# BBB_Learning_Board_0B.net
KiCad netlist of a schematic drawn in EAGLE
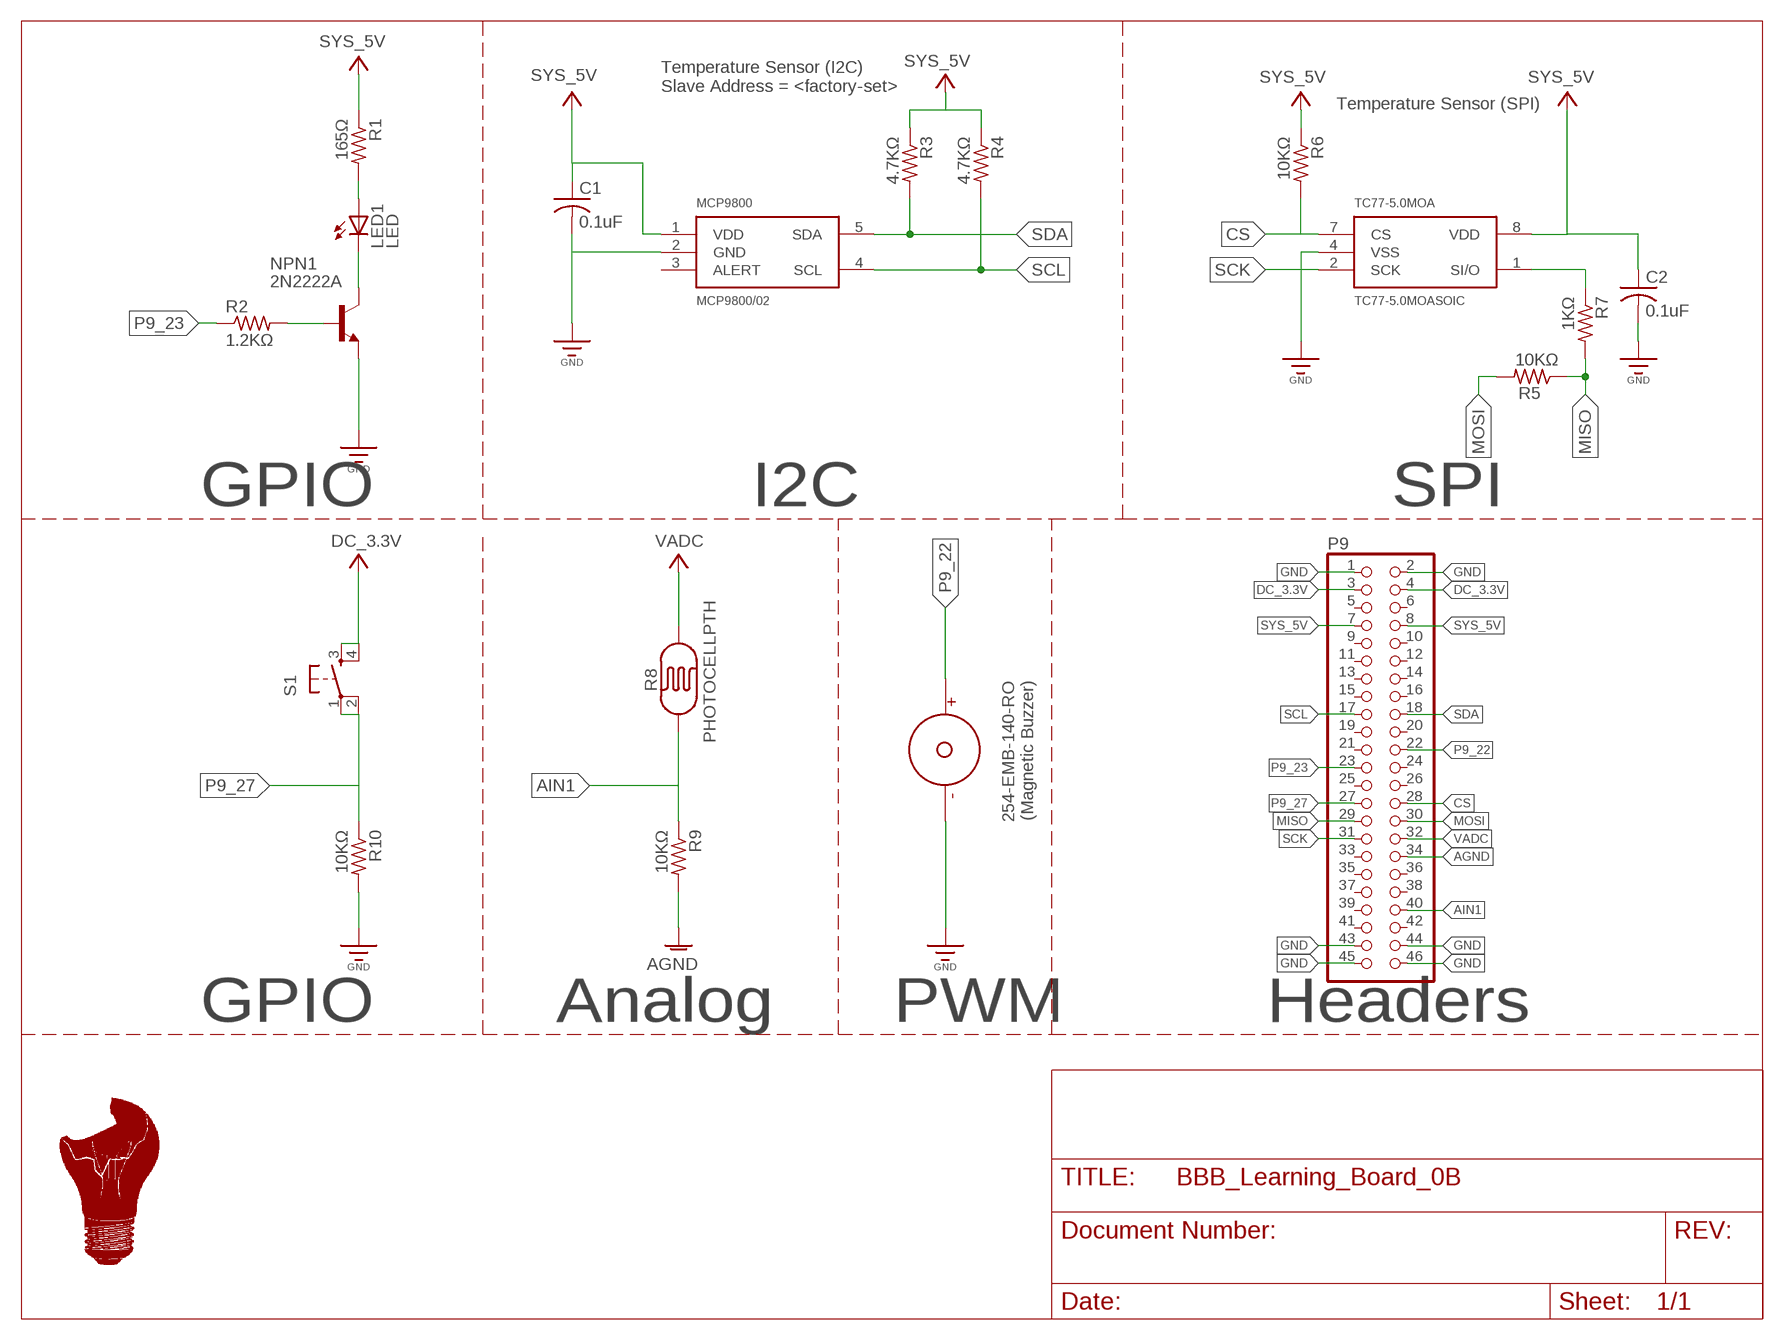
[diagram p0: schematic, sheet 1]

(export (version "E")
  (design (tool "Eeschema 10.0.6"))
  (components
    (comp (ref "C1")
      (value "0.1uF")
      (footprint "eagle-import:C0805")
      (libsource (lib "eagle-import") (part "C-USC0805"))
    )
    (comp (ref "C2")
      (value "0.1uF")
      (footprint "eagle-import:C0805")
      (libsource (lib "eagle-import") (part "C-USC0805"))
    )
    (comp (ref "LED1")
      (value "LED")
      (footprint "eagle-import:LED5MM")
      (libsource (lib "eagle-import") (part "LED"))
    )
    (comp (ref "MCP9800")
      (value "MCP9800/02")
      (footprint "eagle-import:SOT23-5")
      (libsource (lib "eagle-import") (part "MCP9800/02"))
    )
    (comp (ref "NPN1")
      (value "2N2222A")
      (footprint "eagle-import:PINHD-1X3")
      (libsource (lib "eagle-import") (part "2N2222A"))
    )
    (comp (ref "P9")
      (value "PINHD-2X23")
      (footprint "eagle-import:2X23")
      (libsource (lib "eagle-import") (part "PINHD-2X23"))
    )
    (comp (ref "R1")
      (value "165Ω")
      (footprint "eagle-import:R0805")
      (libsource (lib "eagle-import") (part "R-US_R0805"))
    )
    (comp (ref "R2")
      (value "1.2KΩ")
      (footprint "eagle-import:R0805")
      (libsource (lib "eagle-import") (part "R-US_R0805"))
    )
    (comp (ref "R3")
      (value "4.7KΩ")
      (footprint "eagle-import:R0805")
      (libsource (lib "eagle-import") (part "R-US_R0805"))
    )
    (comp (ref "R4")
      (value "4.7KΩ")
      (footprint "eagle-import:R0805")
      (libsource (lib "eagle-import") (part "R-US_R0805"))
    )
    (comp (ref "R5")
      (value "10KΩ")
      (footprint "eagle-import:R0805")
      (libsource (lib "eagle-import") (part "R-US_R0805"))
    )
    (comp (ref "R6")
      (value "10KΩ")
      (footprint "eagle-import:R0805")
      (libsource (lib "eagle-import") (part "R-US_R0805"))
    )
    (comp (ref "R7")
      (value "1KΩ")
      (footprint "eagle-import:R0805")
      (libsource (lib "eagle-import") (part "R-US_R0805"))
    )
    (comp (ref "R8")
      (value "PHOTOCELLPTH")
      (footprint "eagle-import:PHOTOCELL")
      (libsource (lib "eagle-import") (part "PHOTOCELLPTH"))
    )
    (comp (ref "R9")
      (value "10KΩ")
      (footprint "eagle-import:R0805")
      (libsource (lib "eagle-import") (part "R-US_R0805"))
    )
    (comp (ref "R10")
      (value "10KΩ")
      (footprint "eagle-import:R0805")
      (libsource (lib "eagle-import") (part "R-US_R0805"))
    )
    (comp (ref "S1")
      (value "TAC_SWITCHPTH")
      (footprint "eagle-import:TACTILE-PTH")
      (libsource (lib "eagle-import") (part "TAC_SWITCHPTH"))
    )
    (comp (ref "TC77-5.0MOA")
      (value "TC77-5.0MOASOIC")
      (footprint "eagle-import:SOIC-8")
      (libsource (lib "eagle-import") (part "TC77-5.0MOASOIC"))
    )
    (comp (ref "U$6")
      (value "254-EMB-140-RO")
      (footprint "eagle-import:254-EMB-140-RO")
      (libsource (lib "eagle-import") (part "254-EMB-140-RO"))
    )
    (comp (ref "U$7")
      (value "LIGHTBULB_LOGOBOTTOM")
      (footprint "eagle-import:LIGHTBULB_LOGO_BOTTOM-2_54CM2")
      (libsource (lib "eagle-import") (part "LIGHTBULB_LOGOBOTTOM"))
    )
  )
  (nets
    (net (code "1") (name "AGND") (class "Default")
      (node (ref "P9") (pin "34") (pinfunction "34_34") (pintype "passive"))
      (node (ref "R9") (pin "2") (pinfunction "2_2") (pintype "passive"))
    )
    (net (code "2") (name "AIN1") (class "Default")
      (node (ref "P9") (pin "40") (pinfunction "40_40") (pintype "passive"))
      (node (ref "R8") (pin "1") (pinfunction "P$1_1") (pintype "bidirectional"))
      (node (ref "R9") (pin "1") (pinfunction "1_1") (pintype "passive"))
    )
    (net (code "3") (name "CS") (class "Default")
      (node (ref "P9") (pin "28") (pinfunction "28_28") (pintype "passive"))
      (node (ref "R6") (pin "2") (pinfunction "2_2") (pintype "passive"))
      (node (ref "TC77-5.0MOA") (pin "7") (pinfunction "CS_7") (pintype "bidirectional"))
    )
    (net (code "4") (name "DC_3.3V") (class "Default")
      (node (ref "P9") (pin "3") (pinfunction "3_3") (pintype "passive"))
      (node (ref "P9") (pin "4") (pinfunction "4_4") (pintype "passive"))
      (node (ref "S1") (pin "3") (pinfunction "3_3") (pintype "passive"))
      (node (ref "S1") (pin "4") (pinfunction "4_4") (pintype "passive"))
    )
    (net (code "5") (name "GND") (class "Default")
      (node (ref "C1") (pin "2") (pinfunction "2_2") (pintype "passive"))
      (node (ref "C2") (pin "2") (pinfunction "2_2") (pintype "passive"))
      (node (ref "MCP9800") (pin "2") (pinfunction "GND_2") (pintype "bidirectional"))
      (node (ref "NPN1") (pin "1") (pinfunction "E_1") (pintype "passive"))
      (node (ref "P9") (pin "1") (pinfunction "1_1") (pintype "passive"))
      (node (ref "P9") (pin "2") (pinfunction "2_2") (pintype "passive"))
      (node (ref "P9") (pin "43") (pinfunction "43_43") (pintype "passive"))
      (node (ref "P9") (pin "44") (pinfunction "44_44") (pintype "passive"))
      (node (ref "P9") (pin "45") (pinfunction "45_45") (pintype "passive"))
      (node (ref "P9") (pin "46") (pinfunction "46_46") (pintype "passive"))
      (node (ref "R10") (pin "2") (pinfunction "2_2") (pintype "passive"))
      (node (ref "TC77-5.0MOA") (pin "4") (pinfunction "VSS_4") (pintype "power_in"))
      (node (ref "U$6") (pin "NEGATIVE") (pinfunction "NEGATIVE_NEGATIVE") (pintype "bidirectional"))
    )
    (net (code "6") (name "MISO") (class "Default")
      (node (ref "P9") (pin "29") (pinfunction "29_29") (pintype "passive"))
      (node (ref "R5") (pin "1") (pinfunction "1_1") (pintype "passive"))
      (node (ref "R7") (pin "2") (pinfunction "2_2") (pintype "passive"))
    )
    (net (code "7") (name "MOSI") (class "Default")
      (node (ref "P9") (pin "30") (pinfunction "30_30") (pintype "passive"))
      (node (ref "R5") (pin "2") (pinfunction "2_2") (pintype "passive"))
    )
    (net (code "8") (name "Net-(LED1-A)") (class "Default")
      (node (ref "LED1") (pin "ANODE") (pinfunction "A_ANODE") (pintype "passive"))
      (node (ref "R1") (pin "2") (pinfunction "2_2") (pintype "passive"))
    )
    (net (code "9") (name "Net-(LED1-C)") (class "Default")
      (node (ref "LED1") (pin "CATHODE") (pinfunction "C_CATHODE") (pintype "passive"))
      (node (ref "NPN1") (pin "3") (pinfunction "C_3") (pintype "passive"))
    )
    (net (code "10") (name "Net-(NPN1-B)") (class "Default")
      (node (ref "NPN1") (pin "2") (pinfunction "B_2") (pintype "passive"))
      (node (ref "R2") (pin "2") (pinfunction "2_2") (pintype "passive"))
    )
    (net (code "11") (name "Net-(TC77-5.0MOA-SI{slash}O)") (class "Default")
      (node (ref "R7") (pin "1") (pinfunction "1_1") (pintype "passive"))
      (node (ref "TC77-5.0MOA") (pin "1") (pinfunction "SI/O_1") (pintype "bidirectional"))
    )
    (net (code "12") (name "P9_22") (class "Default")
      (node (ref "P9") (pin "22") (pinfunction "22_22") (pintype "passive"))
      (node (ref "U$6") (pin "POSITIVE") (pinfunction "POSITIVE_POSITIVE") (pintype "bidirectional"))
    )
    (net (code "13") (name "P9_23") (class "Default")
      (node (ref "P9") (pin "23") (pinfunction "23_23") (pintype "passive"))
      (node (ref "R2") (pin "1") (pinfunction "1_1") (pintype "passive"))
    )
    (net (code "14") (name "P9_27") (class "Default")
      (node (ref "P9") (pin "27") (pinfunction "27_27") (pintype "passive"))
      (node (ref "R10") (pin "1") (pinfunction "1_1") (pintype "passive"))
      (node (ref "S1") (pin "1") (pinfunction "1_1") (pintype "passive"))
      (node (ref "S1") (pin "2") (pinfunction "2_2") (pintype "passive"))
    )
    (net (code "15") (name "SCK") (class "Default")
      (node (ref "P9") (pin "31") (pinfunction "31_31") (pintype "passive"))
      (node (ref "TC77-5.0MOA") (pin "2") (pinfunction "SCK_2") (pintype "bidirectional"))
    )
    (net (code "16") (name "SCL") (class "Default")
      (node (ref "MCP9800") (pin "4") (pinfunction "SCL_4") (pintype "bidirectional"))
      (node (ref "P9") (pin "17") (pinfunction "17_17") (pintype "passive"))
      (node (ref "R4") (pin "2") (pinfunction "2_2") (pintype "passive"))
    )
    (net (code "17") (name "SDA") (class "Default")
      (node (ref "MCP9800") (pin "5") (pinfunction "SDA_5") (pintype "bidirectional"))
      (node (ref "P9") (pin "18") (pinfunction "18_18") (pintype "passive"))
      (node (ref "R3") (pin "2") (pinfunction "2_2") (pintype "passive"))
    )
    (net (code "18") (name "SYS_5V") (class "Default")
      (node (ref "C1") (pin "1") (pinfunction "1_1") (pintype "passive"))
      (node (ref "C2") (pin "1") (pinfunction "1_1") (pintype "passive"))
      (node (ref "MCP9800") (pin "1") (pinfunction "VDD_1") (pintype "bidirectional"))
      (node (ref "P9") (pin "7") (pinfunction "7_7") (pintype "passive"))
      (node (ref "P9") (pin "8") (pinfunction "8_8") (pintype "passive"))
      (node (ref "R1") (pin "1") (pinfunction "1_1") (pintype "passive"))
      (node (ref "R3") (pin "1") (pinfunction "1_1") (pintype "passive"))
      (node (ref "R4") (pin "1") (pinfunction "1_1") (pintype "passive"))
      (node (ref "R6") (pin "1") (pinfunction "1_1") (pintype "passive"))
      (node (ref "TC77-5.0MOA") (pin "8") (pinfunction "VDD_8") (pintype "power_in"))
    )
    (net (code "19") (name "VADC") (class "Default")
      (node (ref "P9") (pin "32") (pinfunction "32_32") (pintype "passive"))
      (node (ref "R8") (pin "2") (pinfunction "P$2_2") (pintype "bidirectional"))
    )
    (net (code "20") (name "unconnected-(MCP9800-ALERT-Pad3)") (class "Default")
      (node (ref "MCP9800") (pin "3") (pinfunction "ALERT_3") (pintype "bidirectional"))
    )
    (net (code "21") (name "unconnected-(P9-Pad5)") (class "Default")
      (node (ref "P9") (pin "5") (pinfunction "5_5") (pintype "passive"))
    )
    (net (code "22") (name "unconnected-(P9-Pad6)") (class "Default")
      (node (ref "P9") (pin "6") (pinfunction "6_6") (pintype "passive"))
    )
    (net (code "23") (name "unconnected-(P9-Pad9)") (class "Default")
      (node (ref "P9") (pin "9") (pinfunction "9_9") (pintype "passive"))
    )
    (net (code "24") (name "unconnected-(P9-Pad10)") (class "Default")
      (node (ref "P9") (pin "10") (pinfunction "10_10") (pintype "passive"))
    )
    (net (code "25") (name "unconnected-(P9-Pad11)") (class "Default")
      (node (ref "P9") (pin "11") (pinfunction "11_11") (pintype "passive"))
    )
    (net (code "26") (name "unconnected-(P9-Pad12)") (class "Default")
      (node (ref "P9") (pin "12") (pinfunction "12_12") (pintype "passive"))
    )
    (net (code "27") (name "unconnected-(P9-Pad13)") (class "Default")
      (node (ref "P9") (pin "13") (pinfunction "13_13") (pintype "passive"))
    )
    (net (code "28") (name "unconnected-(P9-Pad14)") (class "Default")
      (node (ref "P9") (pin "14") (pinfunction "14_14") (pintype "passive"))
    )
    (net (code "29") (name "unconnected-(P9-Pad15)") (class "Default")
      (node (ref "P9") (pin "15") (pinfunction "15_15") (pintype "passive"))
    )
    (net (code "30") (name "unconnected-(P9-Pad16)") (class "Default")
      (node (ref "P9") (pin "16") (pinfunction "16_16") (pintype "passive"))
    )
    (net (code "31") (name "unconnected-(P9-Pad19)") (class "Default")
      (node (ref "P9") (pin "19") (pinfunction "19_19") (pintype "passive"))
    )
    (net (code "32") (name "unconnected-(P9-Pad20)") (class "Default")
      (node (ref "P9") (pin "20") (pinfunction "20_20") (pintype "passive"))
    )
    (net (code "33") (name "unconnected-(P9-Pad21)") (class "Default")
      (node (ref "P9") (pin "21") (pinfunction "21_21") (pintype "passive"))
    )
    (net (code "34") (name "unconnected-(P9-Pad24)") (class "Default")
      (node (ref "P9") (pin "24") (pinfunction "24_24") (pintype "passive"))
    )
    (net (code "35") (name "unconnected-(P9-Pad25)") (class "Default")
      (node (ref "P9") (pin "25") (pinfunction "25_25") (pintype "passive"))
    )
    (net (code "36") (name "unconnected-(P9-Pad26)") (class "Default")
      (node (ref "P9") (pin "26") (pinfunction "26_26") (pintype "passive"))
    )
    (net (code "37") (name "unconnected-(P9-Pad33)") (class "Default")
      (node (ref "P9") (pin "33") (pinfunction "33_33") (pintype "passive"))
    )
    (net (code "38") (name "unconnected-(P9-Pad35)") (class "Default")
      (node (ref "P9") (pin "35") (pinfunction "35_35") (pintype "passive"))
    )
    (net (code "39") (name "unconnected-(P9-Pad36)") (class "Default")
      (node (ref "P9") (pin "36") (pinfunction "36_36") (pintype "passive"))
    )
    (net (code "40") (name "unconnected-(P9-Pad37)") (class "Default")
      (node (ref "P9") (pin "37") (pinfunction "37_37") (pintype "passive"))
    )
    (net (code "41") (name "unconnected-(P9-Pad38)") (class "Default")
      (node (ref "P9") (pin "38") (pinfunction "38_38") (pintype "passive"))
    )
    (net (code "42") (name "unconnected-(P9-Pad39)") (class "Default")
      (node (ref "P9") (pin "39") (pinfunction "39_39") (pintype "passive"))
    )
    (net (code "43") (name "unconnected-(P9-Pad41)") (class "Default")
      (node (ref "P9") (pin "41") (pinfunction "41_41") (pintype "passive"))
    )
    (net (code "44") (name "unconnected-(P9-Pad42)") (class "Default")
      (node (ref "P9") (pin "42") (pinfunction "42_42") (pintype "passive"))
    )
  )
)
